# remote-38k-6key.net
KiCad netlist of a schematic drawn in Altium Designer
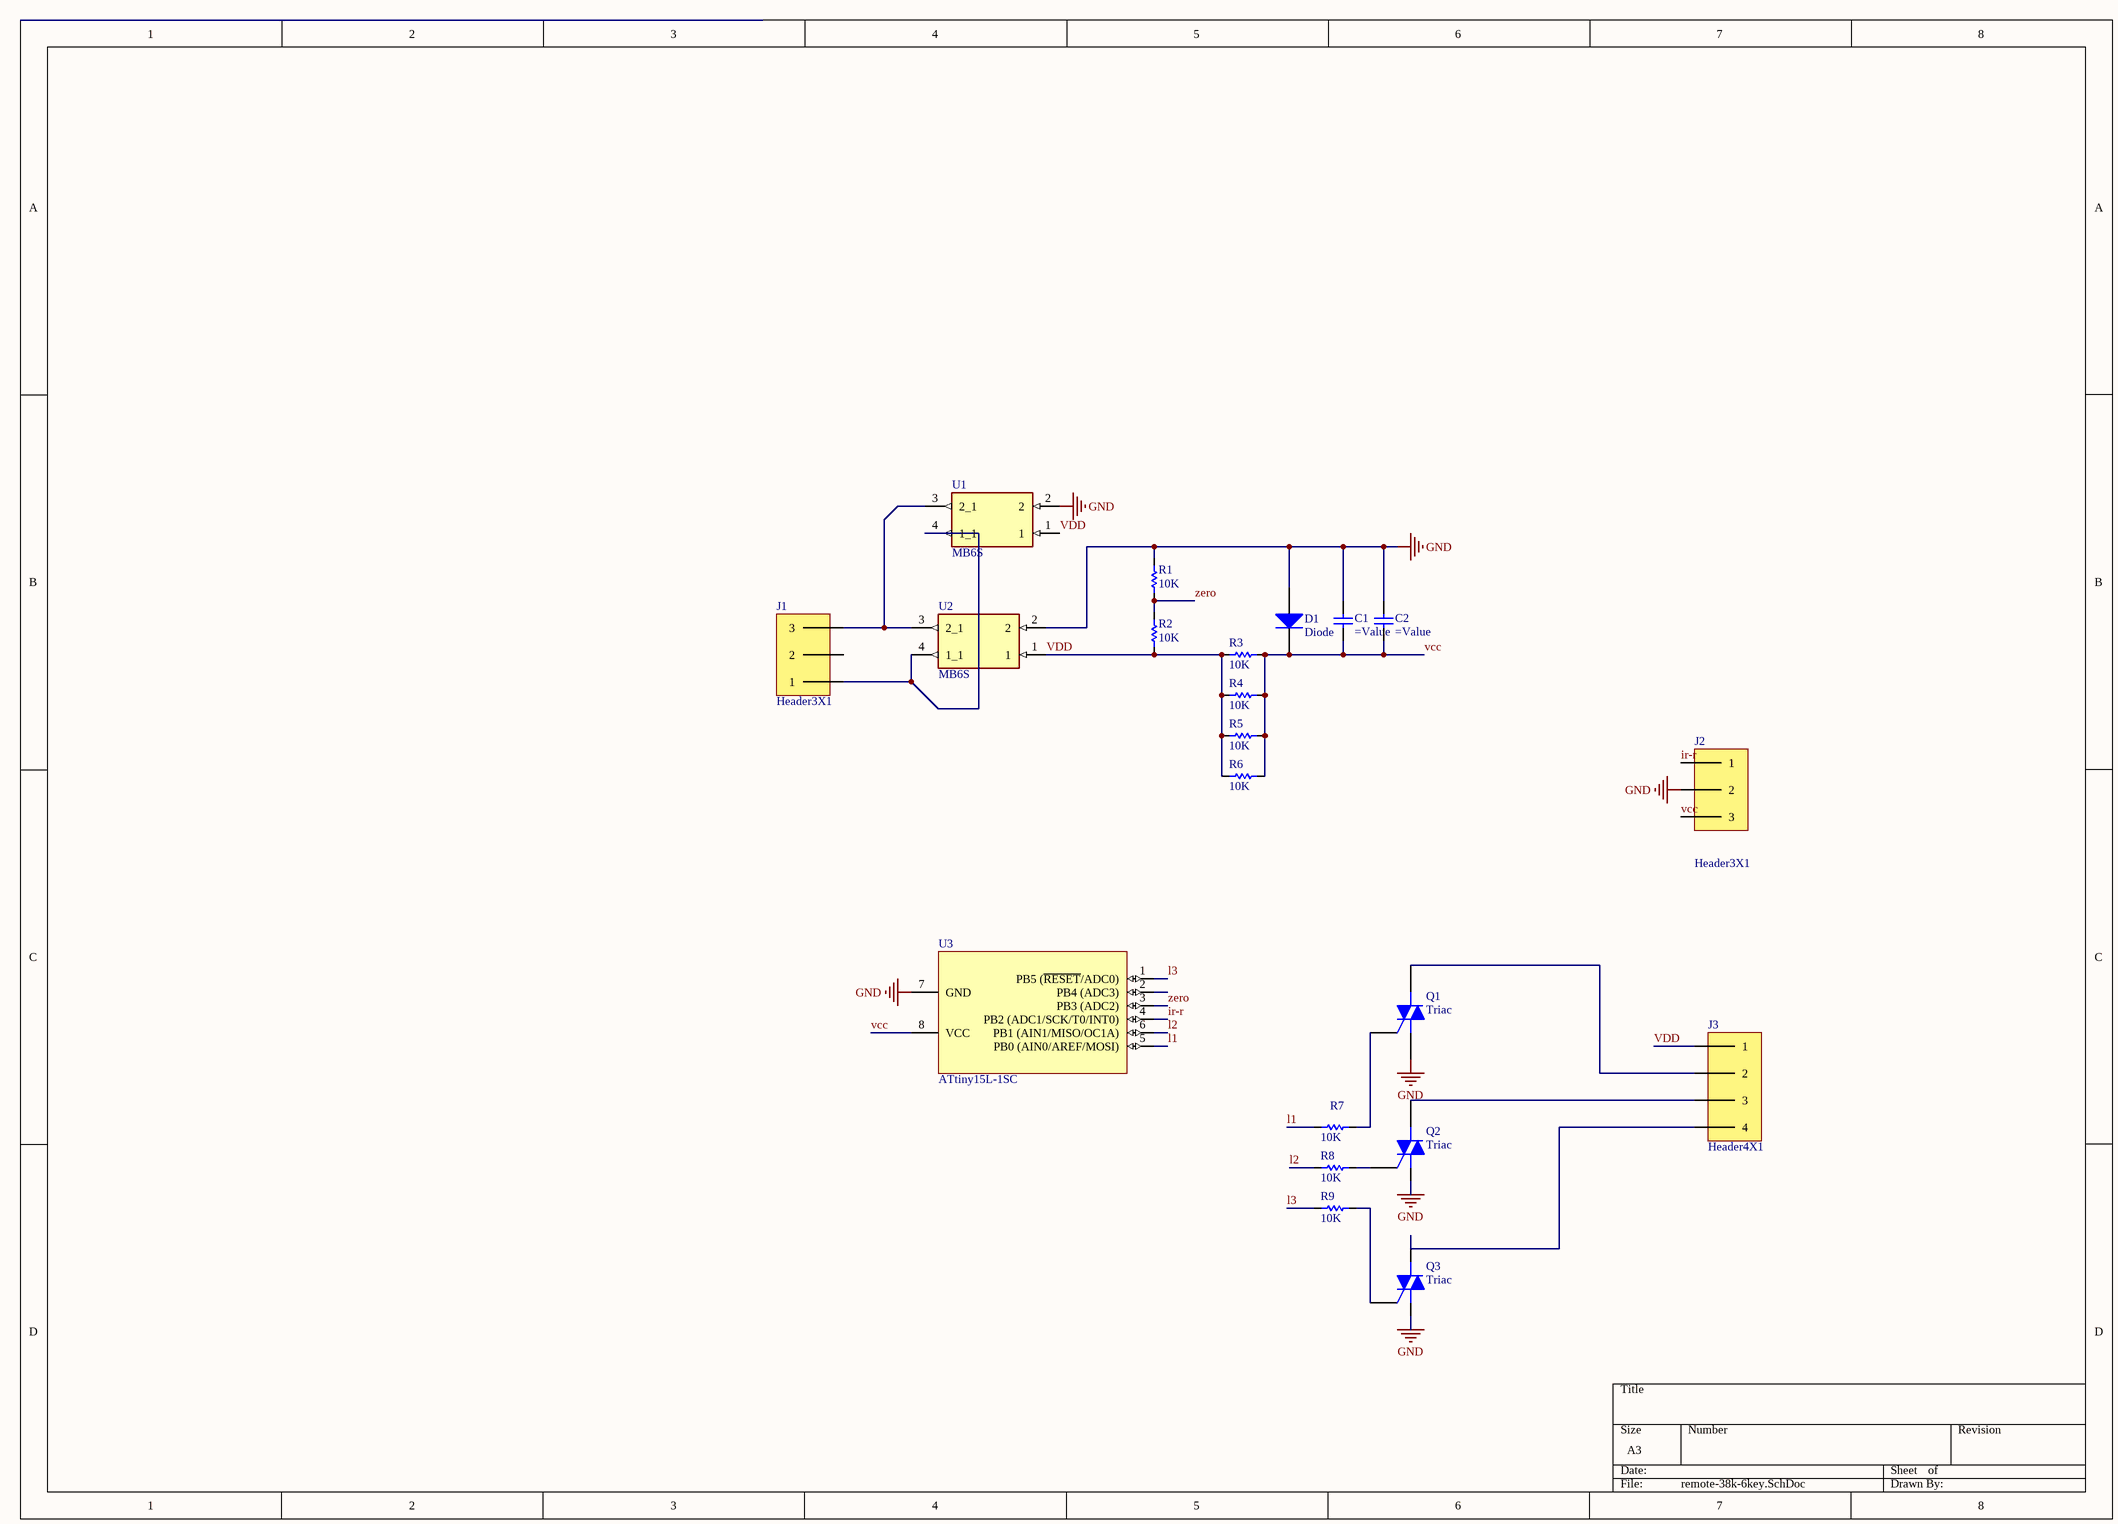
[diagram p0: remote-38k-6key.SchDoc]

(export (version "E")
  (design (tool "Eeschema 10.0.6"))
  (components
    (comp (ref "C1")
      (value "~")
      (footprint "CAP 1206")
      (description "Capacitor")
      (libsource (lib "AltiumLib1") (part "Capacitor"))
    )
    (comp (ref "C2")
      (value "~")
      (footprint "CAP 1206")
      (description "Capacitor")
      (libsource (lib "AltiumLib1") (part "Capacitor"))
    )
    (comp (ref "D1")
      (value "Diode")
      (footprint "C1206")
      (description "Default Diode")
      (fields (field (name "PUBLISHER") "Altium Limited"))
      (libsource (lib "Miscellaneous Devices") (part "Diode"))
    )
    (comp (ref "J1")
      (value "Header3X1")
      (footprint "HEADER 3X1")
      (libsource (lib "AltiumLib1") (part "Header3X1"))
    )
    (comp (ref "J2") (value "Header3X1") (footprint "HEADER 3X1") (libsource (lib "") (part "Header3X1_1")))
    (comp (ref "J3")
      (value "Header4X1")
      (footprint "HEADER 4X1")
      (libsource (lib "AltiumLib1") (part "Header4X1"))
    )
    (comp (ref "Q1")
      (value "Triac")
      (footprint "SOT89N")
      (description "Silicon Bidirectional Triode Thyristor")
      (fields (field (name "PUBLISHER") "Altium Limited"))
      (libsource (lib "Miscellaneous Devices") (part "Triac"))
    )
    (comp (ref "Q2")
      (value "Triac")
      (footprint "SOT89N")
      (description "Silicon Bidirectional Triode Thyristor")
      (fields (field (name "PUBLISHER") "Altium Limited"))
      (libsource (lib "Miscellaneous Devices") (part "Triac"))
    )
    (comp (ref "Q3")
      (value "Triac")
      (footprint "SOT89N")
      (description "Silicon Bidirectional Triode Thyristor")
      (fields (field (name "PUBLISHER") "Altium Limited"))
      (libsource (lib "Miscellaneous Devices") (part "Triac"))
    )
    (comp (ref "R1")
      (value "10K")
      (footprint "RES 1206 (3216X08L)")
      (description "Resistor")
      (fields (field (name "TOLERANCE") "5%") (field (name "POWER") "1/4 W"))
      (libsource (lib "AltiumLib1") (part "Resistor"))
    )
    (comp (ref "R2")
      (value "10K")
      (footprint "RES 1206 (3216X08L)")
      (description "Resistor")
      (fields (field (name "TOLERANCE") "5%") (field (name "POWER") "1/4 W"))
      (libsource (lib "AltiumLib1") (part "Resistor"))
    )
    (comp (ref "R3")
      (value "10K")
      (footprint "RES 2010 (5026X08L)")
      (description "Resistor")
      (fields (field (name "TOLERANCE") "5%") (field (name "POWER") "1/4 W"))
      (libsource (lib "AltiumLib1") (part "Resistor"))
    )
    (comp (ref "R4")
      (value "10K")
      (footprint "RES 2010 (5026X08L)")
      (description "Resistor")
      (fields (field (name "TOLERANCE") "5%") (field (name "POWER") "1/4 W"))
      (libsource (lib "AltiumLib1") (part "Resistor"))
    )
    (comp (ref "R5")
      (value "10K")
      (footprint "RES 2010 (5026X08L)")
      (description "Resistor")
      (fields (field (name "TOLERANCE") "5%") (field (name "POWER") "1/4 W"))
      (libsource (lib "AltiumLib1") (part "Resistor"))
    )
    (comp (ref "R6")
      (value "10K")
      (footprint "RES 2010 (5026X08L)")
      (description "Resistor")
      (fields (field (name "TOLERANCE") "5%") (field (name "POWER") "1/4 W"))
      (libsource (lib "AltiumLib1") (part "Resistor"))
    )
    (comp (ref "R7")
      (value "10K")
      (footprint "RES 1206 (3216X08L)")
      (description "Resistor")
      (fields (field (name "TOLERANCE") "5%") (field (name "POWER") "1/4 W"))
      (libsource (lib "AltiumLib1") (part "Resistor"))
    )
    (comp (ref "R8")
      (value "10K")
      (footprint "RES 1206 (3216X08L)")
      (description "Resistor")
      (fields (field (name "TOLERANCE") "5%") (field (name "POWER") "1/4 W"))
      (libsource (lib "AltiumLib1") (part "Resistor"))
    )
    (comp (ref "R9")
      (value "10K")
      (footprint "RES 1206 (3216X08L)")
      (description "Resistor")
      (fields (field (name "TOLERANCE") "5%") (field (name "POWER") "1/4 W"))
      (libsource (lib "AltiumLib1") (part "Resistor"))
    )
    (comp (ref "U1")
      (value "MB6S")
      (footprint "SOIC245P670X270-4N")
      (description "Bridge Rectifier Single Phase Standard 600V Surface Mount 4-SOIC")
      (fields (field (name "MF") "ON Semiconductor") (field (name "DIGI-KEY_PART_NUMBER") "MB6SCT-ND"))
      (libsource (lib "MB6S") (part "MB6S"))
    )
    (comp (ref "U2")
      (value "MB6S")
      (footprint "SOIC245P670X270-4N")
      (description "Bridge Rectifier Single Phase Standard 600V Surface Mount 4-SOIC")
      (fields (field (name "MF") "ON Semiconductor") (field (name "DIGI-KEY_PART_NUMBER") "MB6SCT-ND"))
      (libsource (lib "MB6S") (part "MB6S"))
    )
    (comp (ref "U3")
      (value "ATtiny15L-1SC")
      (footprint "8S2_N")
      (description "8-Bit AVR Microcontroller with 1K Byte of Flash Memory")
      (fields (field (name "PUBLISHER") "Altium Limited"))
      (libsource (lib "Atmel Microcontroller 8-Bit AVR") (part "ATtiny15L-1SC"))
    )
  )
  (nets
    (net (code "1") (name "/VDD") (class "Default")
      (node (ref "J3") (pin "1") (pinfunction "1_1") (pintype "passive"))
      (node (ref "R2") (pin "1") (pinfunction "1_1") (pintype "passive"))
      (node (ref "R3") (pin "1") (pinfunction "1_1") (pintype "passive"))
      (node (ref "R4") (pin "1") (pinfunction "1_1") (pintype "passive"))
      (node (ref "R5") (pin "1") (pinfunction "1_1") (pintype "passive"))
      (node (ref "R6") (pin "1") (pinfunction "1_1") (pintype "passive"))
      (node (ref "U1") (pin "1") (pinfunction "1_1") (pintype "input"))
      (node (ref "U2") (pin "1") (pinfunction "1_1") (pintype "input"))
    )
    (net (code "2") (name "/ir-r") (class "Default")
      (node (ref "J2") (pin "1") (pinfunction "1_1") (pintype "passive"))
      (node (ref "U3") (pin "4") (pinfunction "PB2_(ADC1/SCK/T0/INT0)_4") (pintype "bidirectional"))
    )
    (net (code "3") (name "/l1") (class "Default")
      (node (ref "R7") (pin "1") (pinfunction "1_1") (pintype "passive"))
      (node (ref "U3") (pin "5") (pinfunction "PB0_(AIN0/AREF/MOSI)_5") (pintype "bidirectional"))
    )
    (net (code "4") (name "/l2") (class "Default")
      (node (ref "R8") (pin "1") (pinfunction "1_1") (pintype "passive"))
      (node (ref "U3") (pin "6") (pinfunction "PB1_(AIN1/MISO/OC1A)_6") (pintype "bidirectional"))
    )
    (net (code "5") (name "/l3") (class "Default")
      (node (ref "R9") (pin "1") (pinfunction "1_1") (pintype "passive"))
      (node (ref "U3") (pin "1") (pinfunction "PB5_(~{RESET}/ADC0)_1") (pintype "bidirectional"))
    )
    (net (code "6") (name "/vcc") (class "Default")
      (node (ref "C1") (pin "1") (pinfunction "+_1") (pintype "passive"))
      (node (ref "C2") (pin "1") (pinfunction "+_1") (pintype "passive"))
      (node (ref "D1") (pin "2") (pinfunction "K_2") (pintype "passive"))
      (node (ref "J2") (pin "3") (pinfunction "3_3") (pintype "passive"))
      (node (ref "R3") (pin "2") (pinfunction "2_2") (pintype "passive"))
      (node (ref "R4") (pin "2") (pinfunction "2_2") (pintype "passive"))
      (node (ref "R5") (pin "2") (pinfunction "2_2") (pintype "passive"))
      (node (ref "R6") (pin "2") (pinfunction "2_2") (pintype "passive"))
      (node (ref "U3") (pin "8") (pinfunction "VCC_8") (pintype "power_in"))
    )
    (net (code "7") (name "/zero") (class "Default")
      (node (ref "R1") (pin "1") (pinfunction "1_1") (pintype "passive"))
      (node (ref "R2") (pin "2") (pinfunction "2_2") (pintype "passive"))
      (node (ref "U3") (pin "3") (pinfunction "PB3_(ADC2)_3") (pintype "bidirectional"))
    )
    (net (code "8") (name "GND") (class "Default")
      (node (ref "C1") (pin "2") (pinfunction "-_2") (pintype "passive"))
      (node (ref "C2") (pin "2") (pinfunction "-_2") (pintype "passive"))
      (node (ref "D1") (pin "1") (pinfunction "A_1") (pintype "passive"))
      (node (ref "J2") (pin "2") (pinfunction "2_2") (pintype "passive"))
      (node (ref "Q1") (pin "1") (pinfunction "M1_1") (pintype "passive"))
      (node (ref "Q2") (pin "1") (pinfunction "M1_1") (pintype "passive"))
      (node (ref "Q3") (pin "1") (pinfunction "M1_1") (pintype "passive"))
      (node (ref "R1") (pin "2") (pinfunction "2_2") (pintype "passive"))
      (node (ref "U1") (pin "2") (pinfunction "2_2") (pintype "input"))
      (node (ref "U2") (pin "2") (pinfunction "2_2") (pintype "input"))
      (node (ref "U3") (pin "7") (pinfunction "GND_7") (pintype "power_in"))
    )
    (net (code "9") (name "Net-(Q1-G)") (class "Default")
      (node (ref "Q1") (pin "3") (pinfunction "G_3") (pintype "passive"))
      (node (ref "R7") (pin "2") (pinfunction "2_2") (pintype "passive"))
    )
    (net (code "10") (name "Net-(Q1-M2)") (class "Default")
      (node (ref "J3") (pin "2") (pinfunction "2_2") (pintype "passive"))
      (node (ref "Q1") (pin "2") (pinfunction "M2_2") (pintype "passive"))
    )
    (net (code "11") (name "Net-(Q2-G)") (class "Default")
      (node (ref "Q2") (pin "3") (pinfunction "G_3") (pintype "passive"))
      (node (ref "R8") (pin "2") (pinfunction "2_2") (pintype "passive"))
    )
    (net (code "12") (name "Net-(Q2-M2)") (class "Default")
      (node (ref "J3") (pin "3") (pinfunction "3_3") (pintype "passive"))
      (node (ref "Q2") (pin "2") (pinfunction "M2_2") (pintype "passive"))
    )
    (net (code "13") (name "Net-(Q3-G)") (class "Default")
      (node (ref "Q3") (pin "3") (pinfunction "G_3") (pintype "passive"))
      (node (ref "R9") (pin "2") (pinfunction "2_2") (pintype "passive"))
    )
    (net (code "14") (name "Net-(Q3-M2)") (class "Default")
      (node (ref "J3") (pin "4") (pinfunction "4_4") (pintype "passive"))
      (node (ref "Q3") (pin "2") (pinfunction "M2_2") (pintype "passive"))
    )
    (net (code "15") (name "Net-(U1-1_1)") (class "Default")
      (node (ref "J1") (pin "1") (pinfunction "1_1") (pintype "passive"))
      (node (ref "U1") (pin "4") (pinfunction "1_1_4") (pintype "output"))
      (node (ref "U2") (pin "4") (pinfunction "1_1_4") (pintype "output"))
    )
    (net (code "16") (name "Net-(U1-2_1)") (class "Default")
      (node (ref "J1") (pin "3") (pinfunction "3_3") (pintype "passive"))
      (node (ref "U1") (pin "3") (pinfunction "2_1_3") (pintype "output"))
      (node (ref "U2") (pin "3") (pinfunction "2_1_3") (pintype "output"))
    )
    (net (code "17") (name "unconnected-(J1-Pad2)") (class "Default")
      (node (ref "J1") (pin "2") (pinfunction "2_2") (pintype "passive"))
    )
    (net (code "18") (name "unconnected-(U3-PB4_(ADC3)-Pad2)") (class "Default")
      (node (ref "U3") (pin "2") (pinfunction "PB4_(ADC3)_2") (pintype "bidirectional"))
    )
  )
)
